# ATtiny84_Base_Schematic_v2.net
KiCad netlist of a schematic drawn in EAGLE
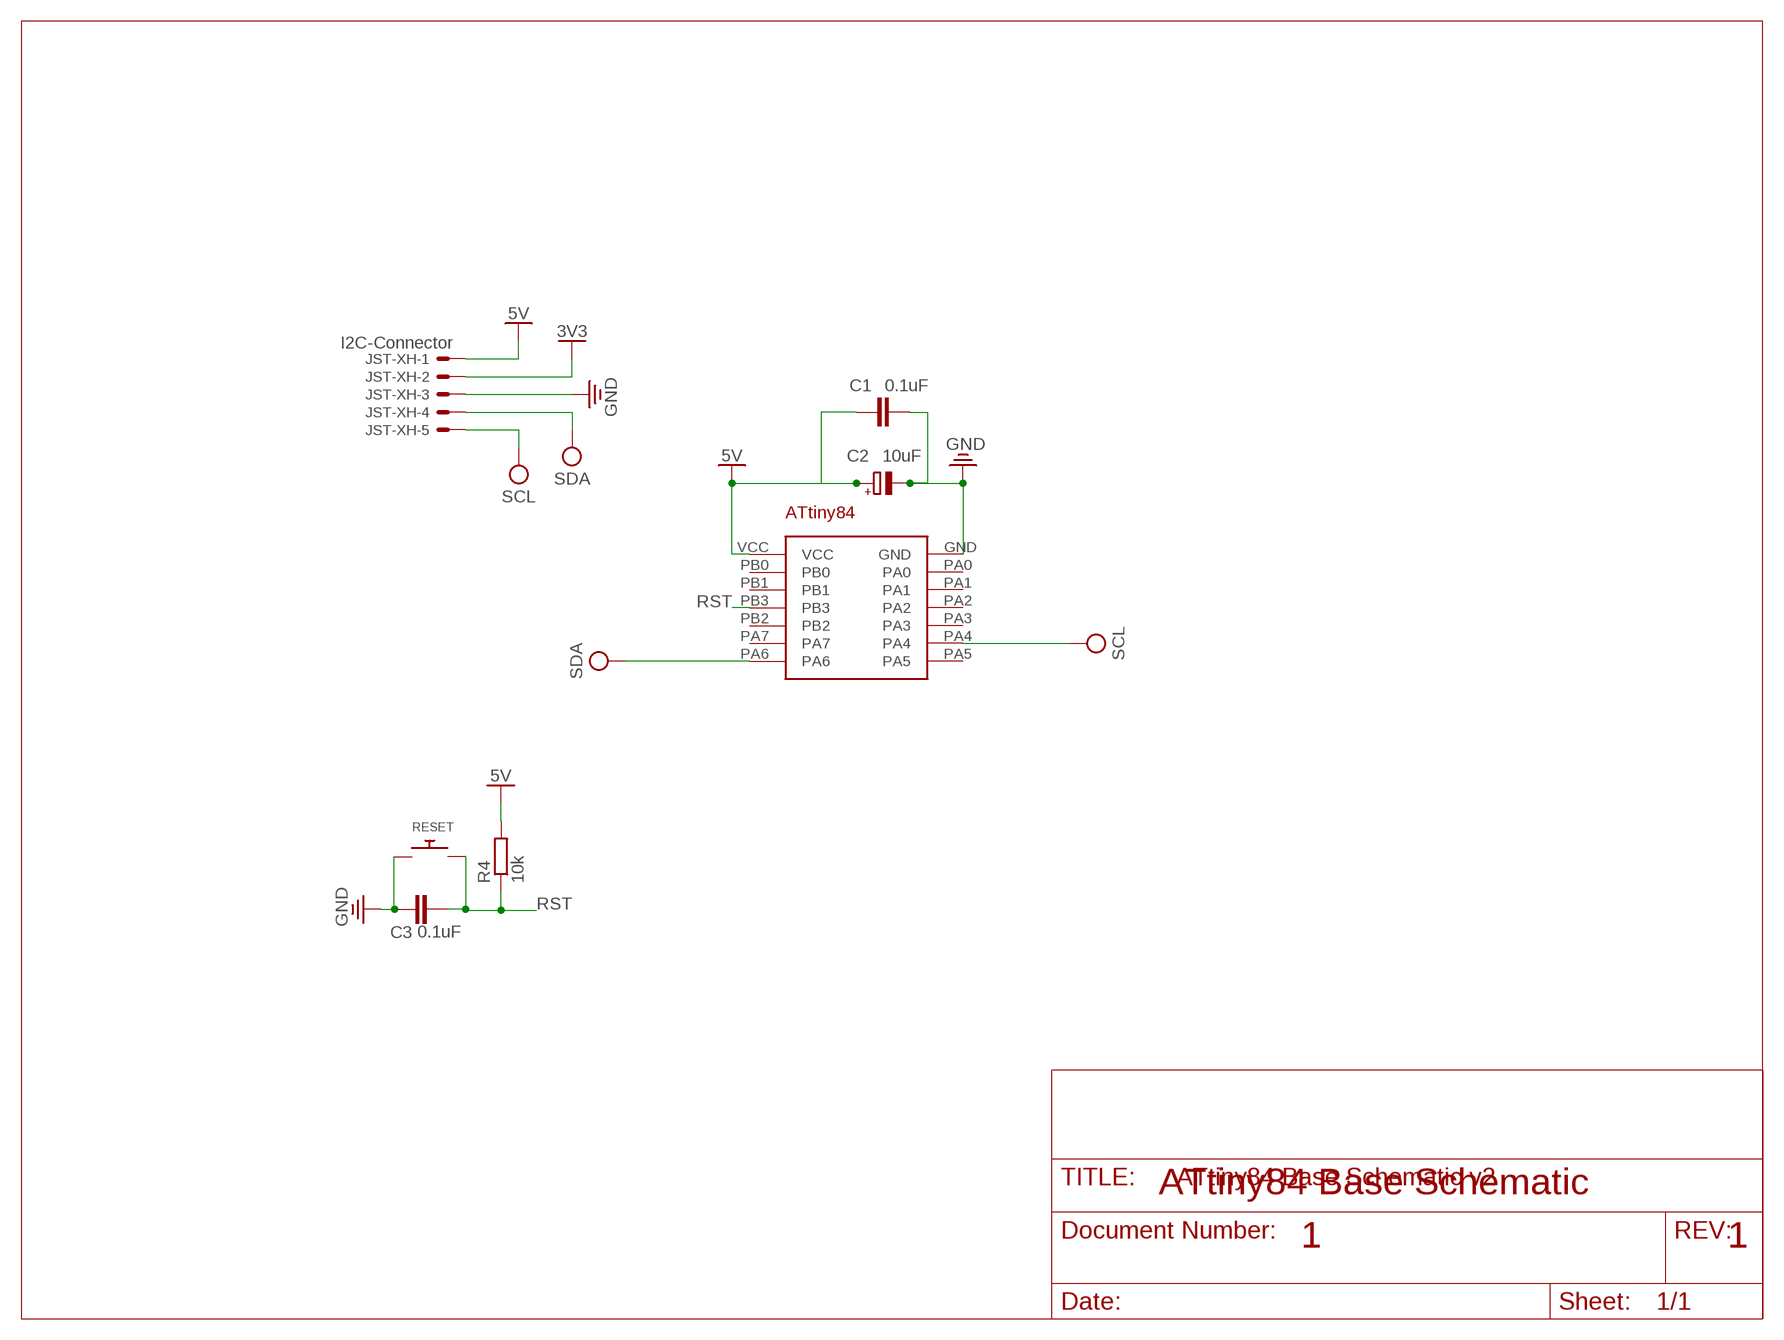
[diagram p0: schematic, sheet 1]

(export (version "E")
  (design (tool "Eeschema 10.0.6"))
  (components
    (comp (ref "C1")
      (value "0.1uF")
      (footprint "eagle-import:C025-025X050")
      (libsource (lib "eagle-import") (part "C-EU025-025X050"))
    )
    (comp (ref "C2")
      (value "10uF")
      (footprint "eagle-import:E5-10,5")
      (libsource (lib "eagle-import") (part "CPOL-EUE5-10.5"))
    )
    (comp (ref "C3")
      (value "0.1uF")
      (footprint "eagle-import:C025-030X050")
      (libsource (lib "eagle-import") (part "C-EU025-030X050"))
    )
    (comp (ref "JST-XH")
      (value "I2C-Connector")
      (footprint "eagle-import:JST-XH-05-PACKAGE-LONG-PAD")
      (libsource (lib "eagle-import") (part "JST-XH-05-PIN-LONG-PAD"))
    )
    (comp (ref "R4")
      (value "10k")
      (footprint "eagle-import:0204_7")
      (libsource (lib "eagle-import") (part "R-EU_0204/7"))
    )
    (comp (ref "RESET")
      (value "SWITCH_PUSHBUTTONEVQ-PE")
      (footprint "eagle-import:TACT_PANA-EVQ")
      (libsource (lib "eagle-import") (part "SWITCH_PUSHBUTTONEVQ-PE"))
    )
    (comp (ref "U$1")
      (value "ATTINY84DIP")
      (footprint "eagle-import:ATTINY84(DIP)")
      (libsource (lib "eagle-import") (part "ATTINY84DIP"))
    )
  )
  (nets
    (net (code "1") (name "/RST") (class "Default")
      (node (ref "C3") (pin "2") (pinfunction "2_2") (pintype "passive"))
      (node (ref "R4") (pin "1") (pinfunction "1_1") (pintype "passive"))
      (node (ref "RESET") (pin "P$2") (pinfunction "P$2_P$2") (pintype "passive"))
      (node (ref "U$1") (pin "PB3") (pinfunction "PB3_PB3") (pintype "bidirectional"))
    )
    (net (code "2") (name "3V3") (class "Default")
      (node (ref "JST-XH") (pin "2") (pinfunction "S_2") (pintype "passive"))
    )
    (net (code "3") (name "5V") (class "Default")
      (node (ref "C1") (pin "1") (pinfunction "1_1") (pintype "passive"))
      (node (ref "C2") (pin "+") (pinfunction "+_+") (pintype "passive"))
      (node (ref "JST-XH") (pin "1") (pinfunction "S_1") (pintype "passive"))
      (node (ref "R4") (pin "2") (pinfunction "2_2") (pintype "passive"))
      (node (ref "U$1") (pin "VCC") (pinfunction "VCC_VCC") (pintype "bidirectional"))
    )
    (net (code "4") (name "GND") (class "Default")
      (node (ref "C1") (pin "2") (pinfunction "2_2") (pintype "passive"))
      (node (ref "C2") (pin "-") (pinfunction "-_-") (pintype "passive"))
      (node (ref "C3") (pin "1") (pinfunction "1_1") (pintype "passive"))
      (node (ref "JST-XH") (pin "3") (pinfunction "S_3") (pintype "passive"))
      (node (ref "RESET") (pin "P$1") (pinfunction "P$1_P$1") (pintype "passive"))
      (node (ref "U$1") (pin "GND") (pinfunction "GND_GND") (pintype "bidirectional"))
    )
    (net (code "5") (name "SCL") (class "Default")
      (node (ref "JST-XH") (pin "5") (pinfunction "S_5") (pintype "passive"))
      (node (ref "U$1") (pin "PA4") (pinfunction "PA4_PA4") (pintype "bidirectional"))
    )
    (net (code "6") (name "SDA") (class "Default")
      (node (ref "JST-XH") (pin "4") (pinfunction "S_4") (pintype "passive"))
      (node (ref "U$1") (pin "PA6") (pinfunction "PA6_PA6") (pintype "bidirectional"))
    )
    (net (code "7") (name "unconnected-(U$1-PadPA0)") (class "Default")
      (node (ref "U$1") (pin "PA0") (pinfunction "PA0_PA0") (pintype "bidirectional"))
    )
    (net (code "8") (name "unconnected-(U$1-PadPA1)") (class "Default")
      (node (ref "U$1") (pin "PA1") (pinfunction "PA1_PA1") (pintype "bidirectional"))
    )
    (net (code "9") (name "unconnected-(U$1-PadPA2)") (class "Default")
      (node (ref "U$1") (pin "PA2") (pinfunction "PA2_PA2") (pintype "bidirectional"))
    )
    (net (code "10") (name "unconnected-(U$1-PadPA3)") (class "Default")
      (node (ref "U$1") (pin "PA3") (pinfunction "PA3_PA3") (pintype "bidirectional"))
    )
    (net (code "11") (name "unconnected-(U$1-PadPA5)") (class "Default")
      (node (ref "U$1") (pin "PA5") (pinfunction "PA5_PA5") (pintype "bidirectional"))
    )
    (net (code "12") (name "unconnected-(U$1-PadPA7)") (class "Default")
      (node (ref "U$1") (pin "PA7") (pinfunction "PA7_PA7") (pintype "bidirectional"))
    )
    (net (code "13") (name "unconnected-(U$1-PadPB0)") (class "Default")
      (node (ref "U$1") (pin "PB0") (pinfunction "PB0_PB0") (pintype "bidirectional"))
    )
    (net (code "14") (name "unconnected-(U$1-PadPB1)") (class "Default")
      (node (ref "U$1") (pin "PB1") (pinfunction "PB1_PB1") (pintype "bidirectional"))
    )
    (net (code "15") (name "unconnected-(U$1-PadPB2)") (class "Default")
      (node (ref "U$1") (pin "PB2") (pinfunction "PB2_PB2") (pintype "bidirectional"))
    )
  )
)
